# MotorAndLight.net
KiCad netlist of a schematic drawn in EAGLE
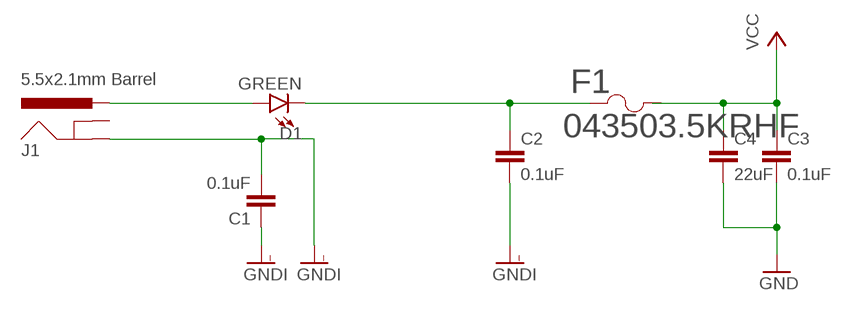
[diagram p0: schematic, sheet 2]
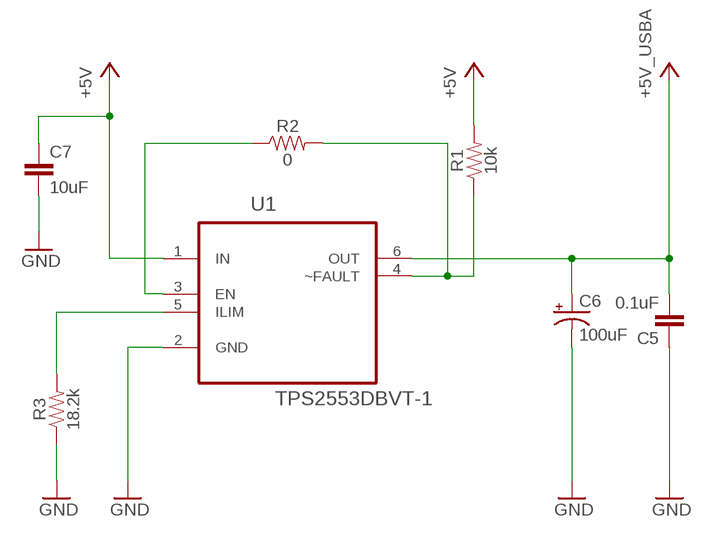
[diagram p1: schematic, sheet 4]
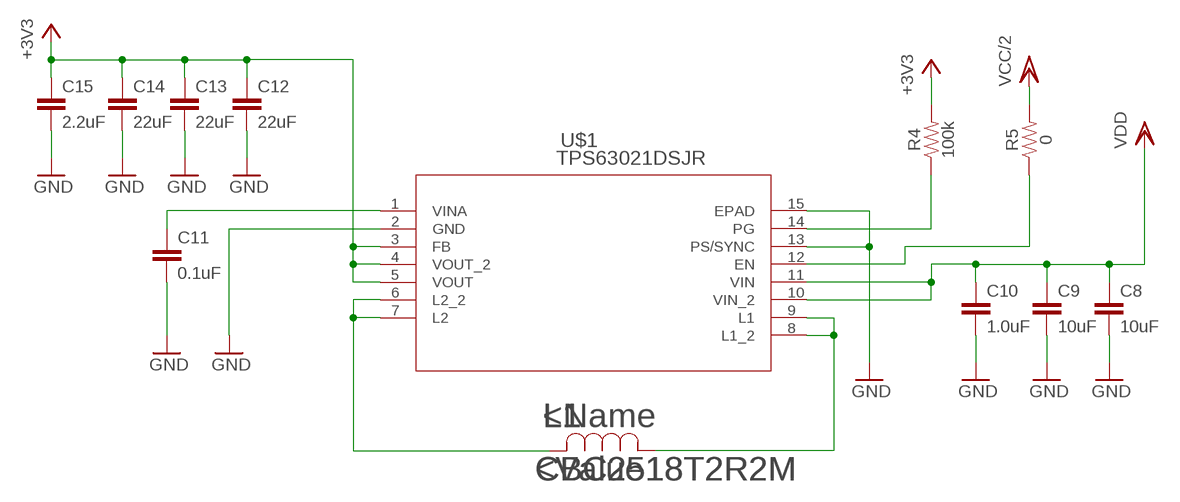
[diagram p2: schematic, sheet 5]
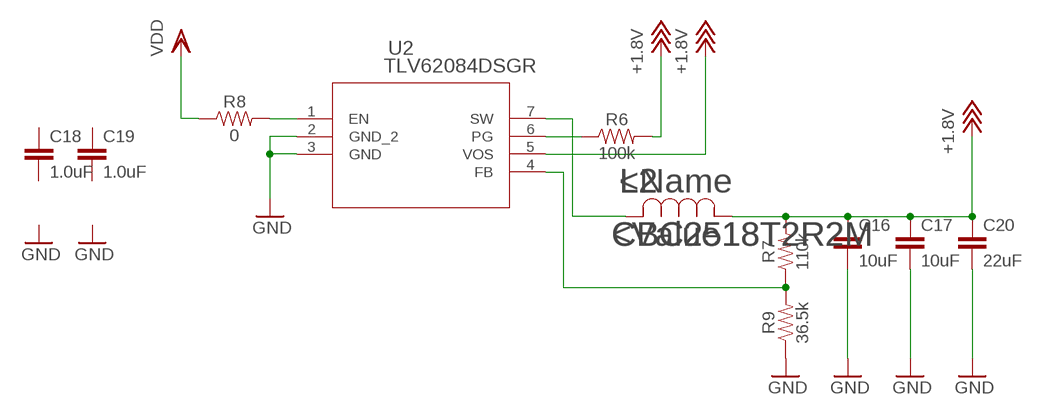
[diagram p3: schematic, sheet 6]

(export (version "E")
  (design (tool "Eeschema 10.0.6"))
  (components
    (comp (ref "C1")
      (value "0.1uF")
      (footprint "eagle-import:0603")
      (libsource (lib "eagle-import") (part "0.1UF-0603-25V-(+80/-20%)"))
    )
    (comp (ref "C2")
      (value "0.1uF")
      (footprint "eagle-import:0603")
      (libsource (lib "eagle-import") (part "0.1UF-0603-25V-(+80/-20%)"))
    )
    (comp (ref "C3")
      (value "0.1uF")
      (footprint "eagle-import:0603")
      (libsource (lib "eagle-import") (part "0.1UF-0603-25V-(+80/-20%)"))
    )
    (comp (ref "C4")
      (value "22uF")
      (footprint "eagle-import:0805")
      (libsource (lib "eagle-import") (part "22UF-0805-6.3V-20%"))
    )
    (comp (ref "D1")
      (value "GREEN")
      (footprint "eagle-import:LED-0603")
      (libsource (lib "eagle-import") (part "LED-GREEN0603"))
    )
    (comp (ref "F1")
      (value "043503.5KRHF")
      (footprint "eagle-import:0435SERIES")
      (libsource (lib "eagle-import") (part "043503.5KRHF"))
    )
    (comp (ref "J1")
      (value "5.5x2.1mm Barrel")
      (footprint "eagle-import:POWER_JACK_SMD")
      (libsource (lib "eagle-import") (part "POWER_JACKSMD"))
    )
    (comp (ref "C16")
      (value "10uF")
      (footprint "eagle-import:0603")
      (libsource (lib "eagle-import") (part "10UF-0603-6.3V-20%"))
    )
    (comp (ref "C17")
      (value "10uF")
      (footprint "eagle-import:0603")
      (libsource (lib "eagle-import") (part "10UF-0603-6.3V-20%"))
    )
    (comp (ref "C18")
      (value "1.0uF")
      (footprint "eagle-import:0603")
      (libsource (lib "eagle-import") (part "1.0UF-0603-16V-10%"))
    )
    (comp (ref "C19")
      (value "1.0uF")
      (footprint "eagle-import:0603")
      (libsource (lib "eagle-import") (part "1.0UF-0603-16V-10%"))
    )
    (comp (ref "C20")
      (value "22uF")
      (footprint "eagle-import:0805")
      (libsource (lib "eagle-import") (part "22UF-0805-6.3V-20%"))
    )
    (comp (ref "L2")
      (value "CBC2518T2R2M")
      (footprint "eagle-import:IND_TAIYO_CBC2518")
      (libsource (lib "eagle-import") (part "CBC2518T2R2M"))
    )
    (comp (ref "R6")
      (value "100k")
      (footprint "eagle-import:0603")
      (libsource (lib "eagle-import") (part "100KOHM-0603-1/10W-1%"))
    )
    (comp (ref "R7")
      (value "110k")
      (footprint "eagle-import:0603")
      (libsource (lib "eagle-import") (part "100KOHM-0603-1/10W-1%"))
    )
    (comp (ref "R8")
      (value "0")
      (footprint "eagle-import:0603")
      (libsource (lib "eagle-import") (part "0OHM-0603-1/10W-5%"))
    )
    (comp (ref "R9")
      (value "36.5k")
      (footprint "eagle-import:0603")
      (libsource (lib "eagle-import") (part "33OHM-0603-1/10W-1%"))
    )
    (comp (ref "U2")
      (value "TLV62084DSGR")
      (footprint "eagle-import:DSG8_0P9X1P6")
      (fields (field (name "MANUFACTURER_PART_NUMBER") "tlv62084dsgr"))
      (libsource (lib "eagle-import") (part "TLV62084DSGR"))
    )
    (comp (ref "C8")
      (value "10uF")
      (footprint "eagle-import:0603")
      (libsource (lib "eagle-import") (part "10UF-0603-6.3V-20%"))
    )
    (comp (ref "C9")
      (value "10uF")
      (footprint "eagle-import:0603")
      (libsource (lib "eagle-import") (part "10UF-0603-6.3V-20%"))
    )
    (comp (ref "C10")
      (value "1.0uF")
      (footprint "eagle-import:0603")
      (libsource (lib "eagle-import") (part "1.0UF-0603-16V-10%"))
    )
    (comp (ref "C11")
      (value "0.1uF")
      (footprint "eagle-import:0603")
      (libsource (lib "eagle-import") (part "0.1UF-0603-25V-(+80/-20%)"))
    )
    (comp (ref "C12")
      (value "22uF")
      (footprint "eagle-import:0805")
      (libsource (lib "eagle-import") (part "22UF-0805-6.3V-20%"))
    )
    (comp (ref "C13")
      (value "22uF")
      (footprint "eagle-import:0805")
      (libsource (lib "eagle-import") (part "22UF-0805-6.3V-20%"))
    )
    (comp (ref "C14")
      (value "22uF")
      (footprint "eagle-import:0805")
      (libsource (lib "eagle-import") (part "22UF-0805-6.3V-20%"))
    )
    (comp (ref "C15")
      (value "2.2uF")
      (footprint "eagle-import:0603")
      (libsource (lib "eagle-import") (part "2.2UF-0603-10V-20%"))
    )
    (comp (ref "L1")
      (value "CBC2518T2R2M")
      (footprint "eagle-import:IND_TAIYO_CBC2518")
      (libsource (lib "eagle-import") (part "CBC2518T2R2M"))
    )
    (comp (ref "R4")
      (value "100k")
      (footprint "eagle-import:0603")
      (libsource (lib "eagle-import") (part "100KOHM-0603-1/10W-1%"))
    )
    (comp (ref "R5")
      (value "0")
      (footprint "eagle-import:0603")
      (libsource (lib "eagle-import") (part "0OHM-0603-1/10W-5%"))
    )
    (comp (ref "U$1")
      (value "TPS63021DSJR")
      (footprint "eagle-import:DSJ14_2P85X1P58")
      (libsource (lib "eagle-import") (part "TPS63021DSJR"))
    )
    (comp (ref "C5")
      (value "0.1uF")
      (footprint "eagle-import:0603")
      (libsource (lib "eagle-import") (part "0.1UF-0603-25V-(+80/-20%)"))
    )
    (comp (ref "C6")
      (value "100uF")
      (footprint "eagle-import:EIA7343")
      (libsource (lib "eagle-import") (part "100UF-POLAR-EIA7343-16V-10%(TANT)"))
    )
    (comp (ref "C7")
      (value "10uF")
      (footprint "eagle-import:0603")
      (libsource (lib "eagle-import") (part "10UF-0603-6.3V-20%"))
    )
    (comp (ref "R1")
      (value "10k")
      (footprint "eagle-import:0603")
      (libsource (lib "eagle-import") (part "10KOHM-0603-1/10W-1%"))
    )
    (comp (ref "R2")
      (value "0")
      (footprint "eagle-import:0603")
      (libsource (lib "eagle-import") (part "0OHM-0603-1/10W-5%"))
    )
    (comp (ref "R3")
      (value "18.2k")
      (footprint "eagle-import:0603")
      (libsource (lib "eagle-import") (part "20KOHM-0603-1/10W-1%"))
    )
    (comp (ref "U1")
      (value "TPS2553DBVT-1")
      (footprint "eagle-import:SOT95P280X145-6N")
      (libsource (lib "eagle-import") (part "TPS2553DBVT-1"))
    )
  )
  (nets
    (net (code "1") (name "+1.8V") (class "Default")
      (node (ref "C16") (pin "1") (pinfunction "1_1") (pintype "passive"))
      (node (ref "C17") (pin "1") (pinfunction "1_1") (pintype "passive"))
      (node (ref "C20") (pin "1") (pinfunction "1_1") (pintype "passive"))
      (node (ref "L2") (pin "1") (pinfunction "1_1") (pintype "passive"))
      (node (ref "R6") (pin "2") (pinfunction "2_2") (pintype "passive"))
      (node (ref "R7") (pin "2") (pinfunction "2_2") (pintype "passive"))
      (node (ref "U2") (pin "5") (pinfunction "VOS_5") (pintype "input"))
    )
    (net (code "2") (name "+3V3") (class "Default")
      (node (ref "C12") (pin "1") (pinfunction "1_1") (pintype "passive"))
      (node (ref "C13") (pin "1") (pinfunction "1_1") (pintype "passive"))
      (node (ref "C14") (pin "1") (pinfunction "1_1") (pintype "passive"))
      (node (ref "C15") (pin "1") (pinfunction "1_1") (pintype "passive"))
      (node (ref "R4") (pin "2") (pinfunction "2_2") (pintype "passive"))
      (node (ref "U$1") (pin "3") (pinfunction "FB_3") (pintype "input"))
      (node (ref "U$1") (pin "4") (pinfunction "VOUT_2_4") (pintype "output"))
      (node (ref "U$1") (pin "5") (pinfunction "VOUT_5") (pintype "output"))
    )
    (net (code "3") (name "+5V") (class "Default")
      (node (ref "C5") (pin "2") (pinfunction "2_2") (pintype "passive"))
      (node (ref "C6") (pin "A") (pinfunction "+_A") (pintype "passive"))
      (node (ref "C7") (pin "1") (pinfunction "1_1") (pintype "passive"))
      (node (ref "R1") (pin "2") (pinfunction "2_2") (pintype "passive"))
      (node (ref "U1") (pin "1") (pinfunction "IN_1") (pintype "power_in"))
      (node (ref "U1") (pin "6") (pinfunction "OUT_6") (pintype "output"))
    )
    (net (code "4") (name "GND") (class "Default")
      (node (ref "C10") (pin "2") (pinfunction "2_2") (pintype "passive"))
      (node (ref "C11") (pin "2") (pinfunction "2_2") (pintype "passive"))
      (node (ref "C12") (pin "2") (pinfunction "2_2") (pintype "passive"))
      (node (ref "C13") (pin "2") (pinfunction "2_2") (pintype "passive"))
      (node (ref "C14") (pin "2") (pinfunction "2_2") (pintype "passive"))
      (node (ref "C15") (pin "2") (pinfunction "2_2") (pintype "passive"))
      (node (ref "C16") (pin "2") (pinfunction "2_2") (pintype "passive"))
      (node (ref "C17") (pin "2") (pinfunction "2_2") (pintype "passive"))
      (node (ref "C20") (pin "2") (pinfunction "2_2") (pintype "passive"))
      (node (ref "C3") (pin "2") (pinfunction "2_2") (pintype "passive"))
      (node (ref "C4") (pin "2") (pinfunction "2_2") (pintype "passive"))
      (node (ref "C5") (pin "1") (pinfunction "1_1") (pintype "passive"))
      (node (ref "C6") (pin "C") (pinfunction "-_C") (pintype "passive"))
      (node (ref "C7") (pin "2") (pinfunction "2_2") (pintype "passive"))
      (node (ref "C8") (pin "2") (pinfunction "2_2") (pintype "passive"))
      (node (ref "C9") (pin "2") (pinfunction "2_2") (pintype "passive"))
      (node (ref "R3") (pin "1") (pinfunction "1_1") (pintype "passive"))
      (node (ref "R9") (pin "1") (pinfunction "1_1") (pintype "passive"))
      (node (ref "U$1") (pin "13") (pinfunction "PS/SYNC_13") (pintype "input"))
      (node (ref "U$1") (pin "15") (pinfunction "EPAD_15") (pintype "passive"))
      (node (ref "U$1") (pin "2") (pinfunction "GND_2") (pintype "power_in"))
      (node (ref "U1") (pin "2") (pinfunction "GND_2") (pintype "passive"))
      (node (ref "U2") (pin "2") (pinfunction "GND_2_2") (pintype "power_in"))
      (node (ref "U2") (pin "3") (pinfunction "GND_3") (pintype "power_in"))
    )
    (net (code "5") (name "GNDI") (class "Default")
      (node (ref "C1") (pin "1") (pinfunction "1_1") (pintype "passive"))
      (node (ref "C1") (pin "2") (pinfunction "2_2") (pintype "passive"))
      (node (ref "C2") (pin "2") (pinfunction "2_2") (pintype "passive"))
      (node (ref "J1") (pin "P$4") (pinfunction "GND_P$4") (pintype "bidirectional"))
    )
    (net (code "6") (name "Net-(C2-Pad1)") (class "Default")
      (node (ref "C2") (pin "1") (pinfunction "1_1") (pintype "passive"))
      (node (ref "D1") (pin "C") (pinfunction "C_C") (pintype "passive"))
      (node (ref "F1") (pin "1") (pinfunction "1_1") (pintype "passive"))
    )
    (net (code "7") (name "Net-(J1-PWR)") (class "Default")
      (node (ref "D1") (pin "A") (pinfunction "A_A") (pintype "passive"))
      (node (ref "J1") (pin "VIN0") (pinfunction "PWR_VIN0") (pintype "bidirectional"))
    )
    (net (code "8") (name "Net-(U$1-EN)") (class "Default")
      (node (ref "R5") (pin "1") (pinfunction "1_1") (pintype "passive"))
      (node (ref "U$1") (pin "12") (pinfunction "EN_12") (pintype "input"))
    )
    (net (code "9") (name "Net-(U$1-L1)") (class "Default")
      (node (ref "L1") (pin "1") (pinfunction "1_1") (pintype "passive"))
      (node (ref "U$1") (pin "8") (pinfunction "L1_2_8") (pintype "input"))
      (node (ref "U$1") (pin "9") (pinfunction "L1_9") (pintype "input"))
    )
    (net (code "10") (name "Net-(U$1-L2)") (class "Default")
      (node (ref "L1") (pin "2") (pinfunction "2_2") (pintype "passive"))
      (node (ref "U$1") (pin "6") (pinfunction "L2_2_6") (pintype "input"))
      (node (ref "U$1") (pin "7") (pinfunction "L2_7") (pintype "input"))
    )
    (net (code "11") (name "Net-(U$1-PG)") (class "Default")
      (node (ref "R4") (pin "1") (pinfunction "1_1") (pintype "passive"))
      (node (ref "U$1") (pin "14") (pinfunction "PG_14") (pintype "output"))
    )
    (net (code "12") (name "Net-(U$1-VINA)") (class "Default")
      (node (ref "C11") (pin "1") (pinfunction "1_1") (pintype "passive"))
      (node (ref "U$1") (pin "1") (pinfunction "VINA_1") (pintype "input"))
    )
    (net (code "13") (name "Net-(U1-EN)") (class "Default")
      (node (ref "R2") (pin "1") (pinfunction "1_1") (pintype "passive"))
      (node (ref "U1") (pin "3") (pinfunction "EN_3") (pintype "input"))
    )
    (net (code "14") (name "Net-(U1-ILIM)") (class "Default")
      (node (ref "R3") (pin "2") (pinfunction "2_2") (pintype "passive"))
      (node (ref "U1") (pin "5") (pinfunction "ILIM_5") (pintype "input"))
    )
    (net (code "15") (name "Net-(U1-~{FAULT})") (class "Default")
      (node (ref "R1") (pin "1") (pinfunction "1_1") (pintype "passive"))
      (node (ref "R2") (pin "2") (pinfunction "2_2") (pintype "passive"))
      (node (ref "U1") (pin "4") (pinfunction "~{FAULT}_4") (pintype "output"))
    )
    (net (code "16") (name "Net-(U2-EN)") (class "Default")
      (node (ref "R8") (pin "2") (pinfunction "2_2") (pintype "passive"))
      (node (ref "U2") (pin "1") (pinfunction "EN_1") (pintype "input"))
    )
    (net (code "17") (name "Net-(U2-FB)") (class "Default")
      (node (ref "R7") (pin "1") (pinfunction "1_1") (pintype "passive"))
      (node (ref "R9") (pin "2") (pinfunction "2_2") (pintype "passive"))
      (node (ref "U2") (pin "4") (pinfunction "FB_4") (pintype "input"))
    )
    (net (code "18") (name "Net-(U2-PG)") (class "Default")
      (node (ref "R6") (pin "1") (pinfunction "1_1") (pintype "passive"))
      (node (ref "U2") (pin "6") (pinfunction "PG_6") (pintype "output"))
    )
    (net (code "19") (name "Net-(U2-SW)") (class "Default")
      (node (ref "L2") (pin "2") (pinfunction "2_2") (pintype "passive"))
      (node (ref "U2") (pin "7") (pinfunction "SW_7") (pintype "passive"))
    )
    (net (code "20") (name "VCC") (class "Default")
      (node (ref "C3") (pin "1") (pinfunction "1_1") (pintype "passive"))
      (node (ref "C4") (pin "1") (pinfunction "1_1") (pintype "passive"))
    )
    (net (code "21") (name "VCC{slash}2") (class "Default")
      (node (ref "R5") (pin "2") (pinfunction "2_2") (pintype "passive"))
    )
    (net (code "22") (name "VDD") (class "Default")
      (node (ref "C10") (pin "1") (pinfunction "1_1") (pintype "passive"))
      (node (ref "C8") (pin "1") (pinfunction "1_1") (pintype "passive"))
      (node (ref "C9") (pin "1") (pinfunction "1_1") (pintype "passive"))
      (node (ref "R8") (pin "1") (pinfunction "1_1") (pintype "passive"))
      (node (ref "U$1") (pin "10") (pinfunction "VIN_2_10") (pintype "input"))
      (node (ref "U$1") (pin "11") (pinfunction "VIN_11") (pintype "input"))
    )
    (net (code "23") (name "unconnected-(C18-Pad1)") (class "Default")
      (node (ref "C18") (pin "1") (pinfunction "1_1") (pintype "passive"))
    )
    (net (code "24") (name "unconnected-(C18-Pad2)") (class "Default")
      (node (ref "C18") (pin "2") (pinfunction "2_2") (pintype "passive"))
    )
    (net (code "25") (name "unconnected-(C19-Pad1)") (class "Default")
      (node (ref "C19") (pin "1") (pinfunction "1_1") (pintype "passive"))
    )
    (net (code "26") (name "unconnected-(C19-Pad2)") (class "Default")
      (node (ref "C19") (pin "2") (pinfunction "2_2") (pintype "passive"))
    )
    (net (code "27") (name "unconnected-(F1-Pad2)") (class "Default")
      (node (ref "F1") (pin "2") (pinfunction "2_2") (pintype "passive"))
    )
    (net (code "28") (name "unconnected-(J1-GNDBREAK-PadGND)") (class "Default")
      (node (ref "J1") (pin "GND") (pinfunction "GNDBREAK_GND") (pintype "bidirectional"))
    )
  )
)
